# Control.net
KiCad netlist of a schematic drawn in Altium Designer
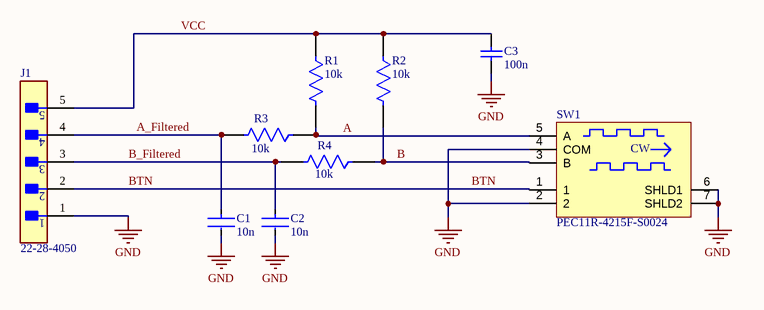
[diagram p0: Control.SchDoc]

(export (version "E")
  (design (tool "Eeschema 10.0.6"))
  (components
    (comp (ref "C1")
      (value "10n")
      (footprint "FP-CL31-IPC_C")
      (description "Cap Ceramic 10nF 100V X7R ±5% SMD 1206 +125°C Embossed T/R")
      (fields (field (name "TOLERANCE") "5%"))
      (libsource (lib "CL31B103JCCNNWC") (part "b4654b650e69147ec39a6b967a45e02"))
    )
    (comp (ref "C2")
      (value "10n")
      (footprint "FP-CL31-IPC_C")
      (description "Cap Ceramic 10nF 100V X7R ±5% SMD 1206 +125°C Embossed T/R")
      (fields (field (name "TOLERANCE") "5%"))
      (libsource (lib "CL31B103JCCNNWC") (part "b4654b650e69147ec39a6b967a45e02"))
    )
    (comp (ref "C3")
      (value "100n")
      (footprint "CAPC1206(3216)100_N")
      (description "CAP 100nF 25V ±5% 1206 (3216 Metric) Thickness 1mm SMD")
      (fields (field (name "TOLERANCE") "Â±5%"))
      (libsource (lib "Altium Content Vault") (part "CAP"))
    )
    (comp (ref "J1")
      (value "22-28-4050")
      (footprint "FP-22-28-4050-MFG")
      (libsource (lib "Altium Content Vault") (part "bf93c07fd2649a848d0ec8585582aab"))
    )
    (comp (ref "R1")
      (value "10k")
      (footprint "FP-CRCW1206-e3-IPC_A")
      (description "RES Thick Film, 10kΩ, 1%, 0.25W, 100ppm/°C, 1206")
      (fields (field (name "TOLERANCE") "1%"))
      (libsource (lib "Altium Content Vault") (part "1029c3af85768c4190bb7ad29bc67b5"))
    )
    (comp (ref "R2")
      (value "10k")
      (footprint "FP-CRCW1206-e3-IPC_A")
      (description "RES Thick Film, 10kΩ, 1%, 0.25W, 100ppm/°C, 1206")
      (fields (field (name "TOLERANCE") "1%"))
      (libsource (lib "Altium Content Vault") (part "1029c3af85768c4190bb7ad29bc67b5"))
    )
    (comp (ref "R3")
      (value "10k")
      (footprint "FP-CRCW1206-e3-IPC_A")
      (description "RES Thick Film, 10kΩ, 1%, 0.25W, 100ppm/°C, 1206")
      (fields (field (name "TOLERANCE") "1%"))
      (libsource (lib "Altium Content Vault") (part "1029c3af85768c4190bb7ad29bc67b5"))
    )
    (comp (ref "R4")
      (value "10k")
      (footprint "FP-CRCW1206-e3-IPC_A")
      (description "RES Thick Film, 10kΩ, 1%, 0.25W, 100ppm/°C, 1206")
      (fields (field (name "TOLERANCE") "1%"))
      (libsource (lib "Altium Content Vault") (part "1029c3af85768c4190bb7ad29bc67b5"))
    )
    (comp (ref "SW1")
      (value "PEC11R-4215F-S0024")
      (footprint "BOUR-PEC11R-4XXXF-SXXXX_V")
      (description "12 mm Incremental Encoder, 24 Detent, -30 to 70 degC, 5-Pin THD, RoHS, Bulk")
      (fields (field (name "MANUFACTURER") "Bourns"))
      (libsource (lib "workspace1") (part "SW-ENCODER-5"))
    )
  )
  (nets
    (net (code "1") (name "/A") (class "Default")
      (node (ref "R1") (pin "2") (pinfunction "2_2") (pintype "passive"))
      (node (ref "R3") (pin "1") (pinfunction "1_1") (pintype "passive"))
      (node (ref "SW1") (pin "5") (pinfunction "A_5") (pintype "passive"))
    )
    (net (code "2") (name "/A_Filtered") (class "Default")
      (node (ref "C1") (pin "1") (pinfunction "1_1") (pintype "passive"))
      (node (ref "J1") (pin "4") (pinfunction "4_4") (pintype "passive"))
      (node (ref "R3") (pin "2") (pinfunction "2_2") (pintype "passive"))
    )
    (net (code "3") (name "/B") (class "Default")
      (node (ref "R2") (pin "2") (pinfunction "2_2") (pintype "passive"))
      (node (ref "R4") (pin "1") (pinfunction "1_1") (pintype "passive"))
      (node (ref "SW1") (pin "3") (pinfunction "B_3") (pintype "passive"))
    )
    (net (code "4") (name "/BTN") (class "Default")
      (node (ref "J1") (pin "2") (pinfunction "2_2") (pintype "passive"))
      (node (ref "SW1") (pin "1") (pinfunction "1_1") (pintype "passive"))
    )
    (net (code "5") (name "/B_Filtered") (class "Default")
      (node (ref "C2") (pin "1") (pinfunction "1_1") (pintype "passive"))
      (node (ref "J1") (pin "3") (pinfunction "3_3") (pintype "passive"))
      (node (ref "R4") (pin "2") (pinfunction "2_2") (pintype "passive"))
    )
    (net (code "6") (name "/VCC") (class "Default")
      (node (ref "C3") (pin "2") (pinfunction "2_2") (pintype "passive"))
      (node (ref "J1") (pin "5") (pinfunction "5_5") (pintype "passive"))
      (node (ref "R1") (pin "1") (pinfunction "1_1") (pintype "passive"))
      (node (ref "R2") (pin "1") (pinfunction "1_1") (pintype "passive"))
    )
    (net (code "7") (name "GND") (class "Default")
      (node (ref "C1") (pin "2") (pinfunction "2_2") (pintype "passive"))
      (node (ref "C2") (pin "2") (pinfunction "2_2") (pintype "passive"))
      (node (ref "C3") (pin "1") (pinfunction "1_1") (pintype "passive"))
      (node (ref "J1") (pin "1") (pinfunction "1_1") (pintype "passive"))
      (node (ref "SW1") (pin "2") (pinfunction "2_2") (pintype "passive"))
      (node (ref "SW1") (pin "4") (pinfunction "COM_4") (pintype "passive"))
      (node (ref "SW1") (pin "6") (pinfunction "SHLD1_6") (pintype "passive"))
      (node (ref "SW1") (pin "7") (pinfunction "SHLD2_7") (pintype "passive"))
    )
  )
)
